# LED_Multichanel_bulb.net
KiCad netlist of a schematic drawn in EasyEDA Pro
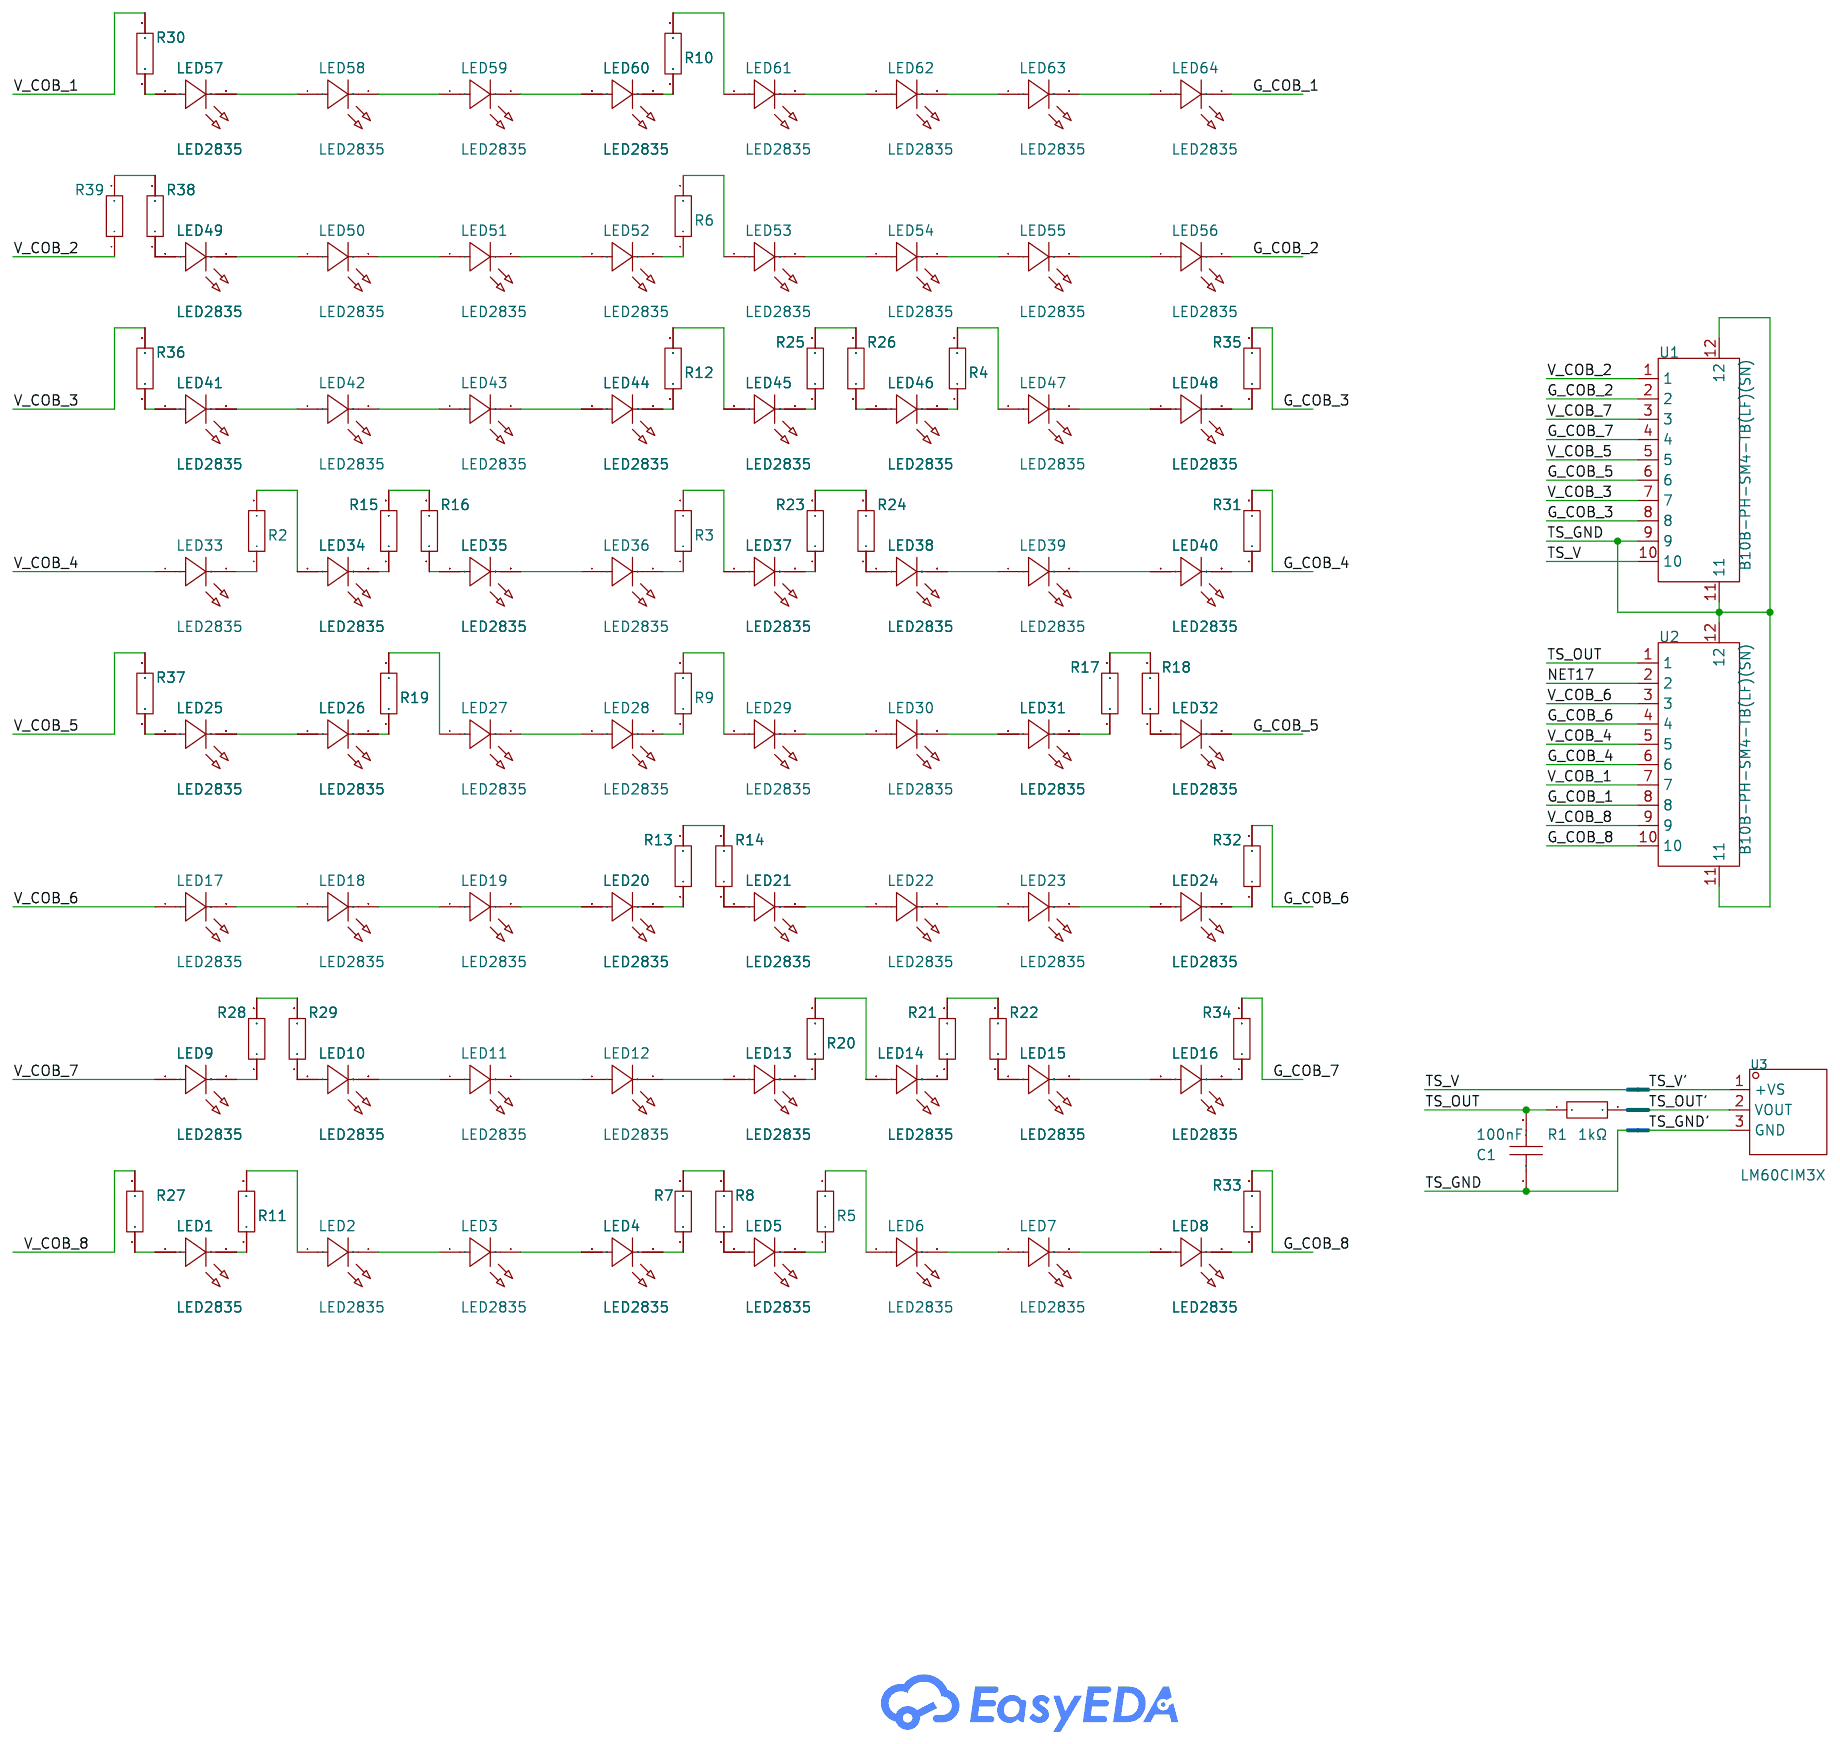
[diagram p0: schematic sheet]

(export (version "E")
  (design (tool "Eeschema 10.0.6"))
  (components
    (comp (ref "C1")
      (value "100nF")
      (footprint "easyedapro:C0805")
      (libsource (lib "easyedapro") (part "CAP"))
    )
    (comp (ref "LED1")
      (value "LED2835")
      (footprint "easyedapro:LED-SMD_L3.5-W2.8_JE2835APO-N-0001A0000-N0000001")
      (fields (field (name "Manufacturer") "WOLFSPEED"))
      (libsource (lib "easyedapro") (part "JE2835APO-N-0001A0000-N0000001"))
    )
    (comp (ref "LED2")
      (value "LED2835")
      (footprint "easyedapro:LED-SMD_L3.5-W2.8_JE2835APO-N-0001A0000-N0000001")
      (fields (field (name "Manufacturer") "WOLFSPEED"))
      (libsource (lib "easyedapro") (part "JE2835APO-N-0001A0000-N0000001"))
    )
    (comp (ref "LED3")
      (value "LED2835")
      (footprint "easyedapro:LED-SMD_L3.5-W2.8_JE2835APO-N-0001A0000-N0000001")
      (fields (field (name "Manufacturer") "WOLFSPEED"))
      (libsource (lib "easyedapro") (part "JE2835APO-N-0001A0000-N0000001"))
    )
    (comp (ref "LED4")
      (value "LED2835")
      (footprint "easyedapro:LED-SMD_L3.5-W2.8_JE2835APO-N-0001A0000-N0000001")
      (fields (field (name "Manufacturer") "WOLFSPEED"))
      (libsource (lib "easyedapro") (part "JE2835APO-N-0001A0000-N0000001"))
    )
    (comp (ref "LED5")
      (value "LED2835")
      (footprint "easyedapro:LED-SMD_L3.5-W2.8_JE2835APO-N-0001A0000-N0000001")
      (fields (field (name "Manufacturer") "WOLFSPEED"))
      (libsource (lib "easyedapro") (part "JE2835APO-N-0001A0000-N0000001"))
    )
    (comp (ref "LED6")
      (value "LED2835")
      (footprint "easyedapro:LED-SMD_L3.5-W2.8_JE2835APO-N-0001A0000-N0000001")
      (fields (field (name "Manufacturer") "WOLFSPEED"))
      (libsource (lib "easyedapro") (part "JE2835APO-N-0001A0000-N0000001"))
    )
    (comp (ref "LED7")
      (value "LED2835")
      (footprint "easyedapro:LED-SMD_L3.5-W2.8_JE2835APO-N-0001A0000-N0000001")
      (fields (field (name "Manufacturer") "WOLFSPEED"))
      (libsource (lib "easyedapro") (part "JE2835APO-N-0001A0000-N0000001"))
    )
    (comp (ref "LED8")
      (value "LED2835")
      (footprint "easyedapro:LED-SMD_L3.5-W2.8_JE2835APO-N-0001A0000-N0000001")
      (fields (field (name "Manufacturer") "WOLFSPEED"))
      (libsource (lib "easyedapro") (part "JE2835APO-N-0001A0000-N0000001"))
    )
    (comp (ref "LED9")
      (value "LED2835")
      (footprint "easyedapro:LED-SMD_L3.5-W2.8_JE2835APO-N-0001A0000-N0000001")
      (fields (field (name "Manufacturer") "WOLFSPEED"))
      (libsource (lib "easyedapro") (part "JE2835APO-N-0001A0000-N0000001"))
    )
    (comp (ref "LED10")
      (value "LED2835")
      (footprint "easyedapro:LED-SMD_L3.5-W2.8_JE2835APO-N-0001A0000-N0000001")
      (fields (field (name "Manufacturer") "WOLFSPEED"))
      (libsource (lib "easyedapro") (part "JE2835APO-N-0001A0000-N0000001"))
    )
    (comp (ref "LED11")
      (value "LED2835")
      (footprint "easyedapro:LED-SMD_L3.5-W2.8_JE2835APO-N-0001A0000-N0000001")
      (fields (field (name "Manufacturer") "WOLFSPEED"))
      (libsource (lib "easyedapro") (part "JE2835APO-N-0001A0000-N0000001"))
    )
    (comp (ref "LED12")
      (value "LED2835")
      (footprint "easyedapro:LED-SMD_L3.5-W2.8_JE2835APO-N-0001A0000-N0000001")
      (fields (field (name "Manufacturer") "WOLFSPEED"))
      (libsource (lib "easyedapro") (part "JE2835APO-N-0001A0000-N0000001"))
    )
    (comp (ref "LED13")
      (value "LED2835")
      (footprint "easyedapro:LED-SMD_L3.5-W2.8_JE2835APO-N-0001A0000-N0000001")
      (fields (field (name "Manufacturer") "WOLFSPEED"))
      (libsource (lib "easyedapro") (part "JE2835APO-N-0001A0000-N0000001"))
    )
    (comp (ref "LED14")
      (value "LED2835")
      (footprint "easyedapro:LED-SMD_L3.5-W2.8_JE2835APO-N-0001A0000-N0000001")
      (fields (field (name "Manufacturer") "WOLFSPEED"))
      (libsource (lib "easyedapro") (part "JE2835APO-N-0001A0000-N0000001"))
    )
    (comp (ref "LED15")
      (value "LED2835")
      (footprint "easyedapro:LED-SMD_L3.5-W2.8_JE2835APO-N-0001A0000-N0000001")
      (fields (field (name "Manufacturer") "WOLFSPEED"))
      (libsource (lib "easyedapro") (part "JE2835APO-N-0001A0000-N0000001"))
    )
    (comp (ref "LED16")
      (value "LED2835")
      (footprint "easyedapro:LED-SMD_L3.5-W2.8_JE2835APO-N-0001A0000-N0000001")
      (fields (field (name "Manufacturer") "WOLFSPEED"))
      (libsource (lib "easyedapro") (part "JE2835APO-N-0001A0000-N0000001"))
    )
    (comp (ref "LED17")
      (value "LED2835")
      (footprint "easyedapro:LED-SMD_L3.5-W2.8_JE2835APO-N-0001A0000-N0000001")
      (fields (field (name "Manufacturer") "WOLFSPEED"))
      (libsource (lib "easyedapro") (part "JE2835APO-N-0001A0000-N0000001"))
    )
    (comp (ref "LED18")
      (value "LED2835")
      (footprint "easyedapro:LED-SMD_L3.5-W2.8_JE2835APO-N-0001A0000-N0000001")
      (fields (field (name "Manufacturer") "WOLFSPEED"))
      (libsource (lib "easyedapro") (part "JE2835APO-N-0001A0000-N0000001"))
    )
    (comp (ref "LED19")
      (value "LED2835")
      (footprint "easyedapro:LED-SMD_L3.5-W2.8_JE2835APO-N-0001A0000-N0000001")
      (fields (field (name "Manufacturer") "WOLFSPEED"))
      (libsource (lib "easyedapro") (part "JE2835APO-N-0001A0000-N0000001"))
    )
    (comp (ref "LED20")
      (value "LED2835")
      (footprint "easyedapro:LED-SMD_L3.5-W2.8_JE2835APO-N-0001A0000-N0000001")
      (fields (field (name "Manufacturer") "WOLFSPEED"))
      (libsource (lib "easyedapro") (part "JE2835APO-N-0001A0000-N0000001"))
    )
    (comp (ref "LED21")
      (value "LED2835")
      (footprint "easyedapro:LED-SMD_L3.5-W2.8_JE2835APO-N-0001A0000-N0000001")
      (fields (field (name "Manufacturer") "WOLFSPEED"))
      (libsource (lib "easyedapro") (part "JE2835APO-N-0001A0000-N0000001"))
    )
    (comp (ref "LED22")
      (value "LED2835")
      (footprint "easyedapro:LED-SMD_L3.5-W2.8_JE2835APO-N-0001A0000-N0000001")
      (fields (field (name "Manufacturer") "WOLFSPEED"))
      (libsource (lib "easyedapro") (part "JE2835APO-N-0001A0000-N0000001"))
    )
    (comp (ref "LED23")
      (value "LED2835")
      (footprint "easyedapro:LED-SMD_L3.5-W2.8_JE2835APO-N-0001A0000-N0000001")
      (fields (field (name "Manufacturer") "WOLFSPEED"))
      (libsource (lib "easyedapro") (part "JE2835APO-N-0001A0000-N0000001"))
    )
    (comp (ref "LED24")
      (value "LED2835")
      (footprint "easyedapro:LED-SMD_L3.5-W2.8_JE2835APO-N-0001A0000-N0000001")
      (fields (field (name "Manufacturer") "WOLFSPEED"))
      (libsource (lib "easyedapro") (part "JE2835APO-N-0001A0000-N0000001"))
    )
    (comp (ref "LED25")
      (value "LED2835")
      (footprint "easyedapro:LED-SMD_L3.5-W2.8_JE2835APO-N-0001A0000-N0000001")
      (fields (field (name "Manufacturer") "WOLFSPEED"))
      (libsource (lib "easyedapro") (part "JE2835APO-N-0001A0000-N0000001"))
    )
    (comp (ref "LED26")
      (value "LED2835")
      (footprint "easyedapro:LED-SMD_L3.5-W2.8_JE2835APO-N-0001A0000-N0000001")
      (fields (field (name "Manufacturer") "WOLFSPEED"))
      (libsource (lib "easyedapro") (part "JE2835APO-N-0001A0000-N0000001"))
    )
    (comp (ref "LED27")
      (value "LED2835")
      (footprint "easyedapro:LED-SMD_L3.5-W2.8_JE2835APO-N-0001A0000-N0000001")
      (fields (field (name "Manufacturer") "WOLFSPEED"))
      (libsource (lib "easyedapro") (part "JE2835APO-N-0001A0000-N0000001"))
    )
    (comp (ref "LED28")
      (value "LED2835")
      (footprint "easyedapro:LED-SMD_L3.5-W2.8_JE2835APO-N-0001A0000-N0000001")
      (fields (field (name "Manufacturer") "WOLFSPEED"))
      (libsource (lib "easyedapro") (part "JE2835APO-N-0001A0000-N0000001"))
    )
    (comp (ref "LED29")
      (value "LED2835")
      (footprint "easyedapro:LED-SMD_L3.5-W2.8_JE2835APO-N-0001A0000-N0000001")
      (fields (field (name "Manufacturer") "WOLFSPEED"))
      (libsource (lib "easyedapro") (part "JE2835APO-N-0001A0000-N0000001"))
    )
    (comp (ref "LED30")
      (value "LED2835")
      (footprint "easyedapro:LED-SMD_L3.5-W2.8_JE2835APO-N-0001A0000-N0000001")
      (fields (field (name "Manufacturer") "WOLFSPEED"))
      (libsource (lib "easyedapro") (part "JE2835APO-N-0001A0000-N0000001"))
    )
    (comp (ref "LED31")
      (value "LED2835")
      (footprint "easyedapro:LED-SMD_L3.5-W2.8_JE2835APO-N-0001A0000-N0000001")
      (fields (field (name "Manufacturer") "WOLFSPEED"))
      (libsource (lib "easyedapro") (part "JE2835APO-N-0001A0000-N0000001"))
    )
    (comp (ref "LED32")
      (value "LED2835")
      (footprint "easyedapro:LED-SMD_L3.5-W2.8_JE2835APO-N-0001A0000-N0000001")
      (fields (field (name "Manufacturer") "WOLFSPEED"))
      (libsource (lib "easyedapro") (part "JE2835APO-N-0001A0000-N0000001"))
    )
    (comp (ref "LED33")
      (value "LED2835")
      (footprint "easyedapro:LED-SMD_L3.5-W2.8_JE2835APO-N-0001A0000-N0000001")
      (fields (field (name "Manufacturer") "WOLFSPEED"))
      (libsource (lib "easyedapro") (part "JE2835APO-N-0001A0000-N0000001"))
    )
    (comp (ref "LED34")
      (value "LED2835")
      (footprint "easyedapro:LED-SMD_L3.5-W2.8_JE2835APO-N-0001A0000-N0000001")
      (fields (field (name "Manufacturer") "WOLFSPEED"))
      (libsource (lib "easyedapro") (part "JE2835APO-N-0001A0000-N0000001"))
    )
    (comp (ref "LED35")
      (value "LED2835")
      (footprint "easyedapro:LED-SMD_L3.5-W2.8_JE2835APO-N-0001A0000-N0000001")
      (fields (field (name "Manufacturer") "WOLFSPEED"))
      (libsource (lib "easyedapro") (part "JE2835APO-N-0001A0000-N0000001"))
    )
    (comp (ref "LED36")
      (value "LED2835")
      (footprint "easyedapro:LED-SMD_L3.5-W2.8_JE2835APO-N-0001A0000-N0000001")
      (fields (field (name "Manufacturer") "WOLFSPEED"))
      (libsource (lib "easyedapro") (part "JE2835APO-N-0001A0000-N0000001"))
    )
    (comp (ref "LED37")
      (value "LED2835")
      (footprint "easyedapro:LED-SMD_L3.5-W2.8_JE2835APO-N-0001A0000-N0000001")
      (fields (field (name "Manufacturer") "WOLFSPEED"))
      (libsource (lib "easyedapro") (part "JE2835APO-N-0001A0000-N0000001"))
    )
    (comp (ref "LED38")
      (value "LED2835")
      (footprint "easyedapro:LED-SMD_L3.5-W2.8_JE2835APO-N-0001A0000-N0000001")
      (fields (field (name "Manufacturer") "WOLFSPEED"))
      (libsource (lib "easyedapro") (part "JE2835APO-N-0001A0000-N0000001"))
    )
    (comp (ref "LED39")
      (value "LED2835")
      (footprint "easyedapro:LED-SMD_L3.5-W2.8_JE2835APO-N-0001A0000-N0000001")
      (fields (field (name "Manufacturer") "WOLFSPEED"))
      (libsource (lib "easyedapro") (part "JE2835APO-N-0001A0000-N0000001"))
    )
    (comp (ref "LED40")
      (value "LED2835")
      (footprint "easyedapro:LED-SMD_L3.5-W2.8_JE2835APO-N-0001A0000-N0000001")
      (fields (field (name "Manufacturer") "WOLFSPEED"))
      (libsource (lib "easyedapro") (part "JE2835APO-N-0001A0000-N0000001"))
    )
    (comp (ref "LED41")
      (value "LED2835")
      (footprint "easyedapro:LED-SMD_L3.5-W2.8_JE2835APO-N-0001A0000-N0000001")
      (fields (field (name "Manufacturer") "WOLFSPEED"))
      (libsource (lib "easyedapro") (part "JE2835APO-N-0001A0000-N0000001"))
    )
    (comp (ref "LED42")
      (value "LED2835")
      (footprint "easyedapro:LED-SMD_L3.5-W2.8_JE2835APO-N-0001A0000-N0000001")
      (fields (field (name "Manufacturer") "WOLFSPEED"))
      (libsource (lib "easyedapro") (part "JE2835APO-N-0001A0000-N0000001"))
    )
    (comp (ref "LED43")
      (value "LED2835")
      (footprint "easyedapro:LED-SMD_L3.5-W2.8_JE2835APO-N-0001A0000-N0000001")
      (fields (field (name "Manufacturer") "WOLFSPEED"))
      (libsource (lib "easyedapro") (part "JE2835APO-N-0001A0000-N0000001"))
    )
    (comp (ref "LED44")
      (value "LED2835")
      (footprint "easyedapro:LED-SMD_L3.5-W2.8_JE2835APO-N-0001A0000-N0000001")
      (fields (field (name "Manufacturer") "WOLFSPEED"))
      (libsource (lib "easyedapro") (part "JE2835APO-N-0001A0000-N0000001"))
    )
    (comp (ref "LED45")
      (value "LED2835")
      (footprint "easyedapro:LED-SMD_L3.5-W2.8_JE2835APO-N-0001A0000-N0000001")
      (fields (field (name "Manufacturer") "WOLFSPEED"))
      (libsource (lib "easyedapro") (part "JE2835APO-N-0001A0000-N0000001"))
    )
    (comp (ref "LED46")
      (value "LED2835")
      (footprint "easyedapro:LED-SMD_L3.5-W2.8_JE2835APO-N-0001A0000-N0000001")
      (fields (field (name "Manufacturer") "WOLFSPEED"))
      (libsource (lib "easyedapro") (part "JE2835APO-N-0001A0000-N0000001"))
    )
    (comp (ref "LED47")
      (value "LED2835")
      (footprint "easyedapro:LED-SMD_L3.5-W2.8_JE2835APO-N-0001A0000-N0000001")
      (fields (field (name "Manufacturer") "WOLFSPEED"))
      (libsource (lib "easyedapro") (part "JE2835APO-N-0001A0000-N0000001"))
    )
    (comp (ref "LED48")
      (value "LED2835")
      (footprint "easyedapro:LED-SMD_L3.5-W2.8_JE2835APO-N-0001A0000-N0000001")
      (fields (field (name "Manufacturer") "WOLFSPEED"))
      (libsource (lib "easyedapro") (part "JE2835APO-N-0001A0000-N0000001"))
    )
    (comp (ref "LED49")
      (value "LED2835")
      (footprint "easyedapro:LED-SMD_L3.5-W2.8_JE2835APO-N-0001A0000-N0000001")
      (fields (field (name "Manufacturer") "WOLFSPEED"))
      (libsource (lib "easyedapro") (part "JE2835APO-N-0001A0000-N0000001"))
    )
    (comp (ref "LED50")
      (value "LED2835")
      (footprint "easyedapro:LED-SMD_L3.5-W2.8_JE2835APO-N-0001A0000-N0000001")
      (fields (field (name "Manufacturer") "WOLFSPEED"))
      (libsource (lib "easyedapro") (part "JE2835APO-N-0001A0000-N0000001"))
    )
    (comp (ref "LED51")
      (value "LED2835")
      (footprint "easyedapro:LED-SMD_L3.5-W2.8_JE2835APO-N-0001A0000-N0000001")
      (fields (field (name "Manufacturer") "WOLFSPEED"))
      (libsource (lib "easyedapro") (part "JE2835APO-N-0001A0000-N0000001"))
    )
    (comp (ref "LED52")
      (value "LED2835")
      (footprint "easyedapro:LED-SMD_L3.5-W2.8_JE2835APO-N-0001A0000-N0000001")
      (fields (field (name "Manufacturer") "WOLFSPEED"))
      (libsource (lib "easyedapro") (part "JE2835APO-N-0001A0000-N0000001"))
    )
    (comp (ref "LED53")
      (value "LED2835")
      (footprint "easyedapro:LED-SMD_L3.5-W2.8_JE2835APO-N-0001A0000-N0000001")
      (fields (field (name "Manufacturer") "WOLFSPEED"))
      (libsource (lib "easyedapro") (part "JE2835APO-N-0001A0000-N0000001"))
    )
    (comp (ref "LED54")
      (value "LED2835")
      (footprint "easyedapro:LED-SMD_L3.5-W2.8_JE2835APO-N-0001A0000-N0000001")
      (fields (field (name "Manufacturer") "WOLFSPEED"))
      (libsource (lib "easyedapro") (part "JE2835APO-N-0001A0000-N0000001"))
    )
    (comp (ref "LED55")
      (value "LED2835")
      (footprint "easyedapro:LED-SMD_L3.5-W2.8_JE2835APO-N-0001A0000-N0000001")
      (fields (field (name "Manufacturer") "WOLFSPEED"))
      (libsource (lib "easyedapro") (part "JE2835APO-N-0001A0000-N0000001"))
    )
    (comp (ref "LED56")
      (value "LED2835")
      (footprint "easyedapro:LED-SMD_L3.5-W2.8_JE2835APO-N-0001A0000-N0000001")
      (fields (field (name "Manufacturer") "WOLFSPEED"))
      (libsource (lib "easyedapro") (part "JE2835APO-N-0001A0000-N0000001"))
    )
    (comp (ref "LED57")
      (value "LED2835")
      (footprint "easyedapro:LED-SMD_L3.5-W2.8_JE2835APO-N-0001A0000-N0000001")
      (fields (field (name "Manufacturer") "WOLFSPEED"))
      (libsource (lib "easyedapro") (part "JE2835APO-N-0001A0000-N0000001"))
    )
    (comp (ref "LED58")
      (value "LED2835")
      (footprint "easyedapro:LED-SMD_L3.5-W2.8_JE2835APO-N-0001A0000-N0000001")
      (fields (field (name "Manufacturer") "WOLFSPEED"))
      (libsource (lib "easyedapro") (part "JE2835APO-N-0001A0000-N0000001"))
    )
    (comp (ref "LED59")
      (value "LED2835")
      (footprint "easyedapro:LED-SMD_L3.5-W2.8_JE2835APO-N-0001A0000-N0000001")
      (fields (field (name "Manufacturer") "WOLFSPEED"))
      (libsource (lib "easyedapro") (part "JE2835APO-N-0001A0000-N0000001"))
    )
    (comp (ref "LED60")
      (value "LED2835")
      (footprint "easyedapro:LED-SMD_L3.5-W2.8_JE2835APO-N-0001A0000-N0000001")
      (fields (field (name "Manufacturer") "WOLFSPEED"))
      (libsource (lib "easyedapro") (part "JE2835APO-N-0001A0000-N0000001"))
    )
    (comp (ref "LED61")
      (value "LED2835")
      (footprint "easyedapro:LED-SMD_L3.5-W2.8_JE2835APO-N-0001A0000-N0000001")
      (fields (field (name "Manufacturer") "WOLFSPEED"))
      (libsource (lib "easyedapro") (part "JE2835APO-N-0001A0000-N0000001"))
    )
    (comp (ref "LED62")
      (value "LED2835")
      (footprint "easyedapro:LED-SMD_L3.5-W2.8_JE2835APO-N-0001A0000-N0000001")
      (fields (field (name "Manufacturer") "WOLFSPEED"))
      (libsource (lib "easyedapro") (part "JE2835APO-N-0001A0000-N0000001"))
    )
    (comp (ref "LED63")
      (value "LED2835")
      (footprint "easyedapro:LED-SMD_L3.5-W2.8_JE2835APO-N-0001A0000-N0000001")
      (fields (field (name "Manufacturer") "WOLFSPEED"))
      (libsource (lib "easyedapro") (part "JE2835APO-N-0001A0000-N0000001"))
    )
    (comp (ref "LED64")
      (value "LED2835")
      (footprint "easyedapro:LED-SMD_L3.5-W2.8_JE2835APO-N-0001A0000-N0000001")
      (fields (field (name "Manufacturer") "WOLFSPEED"))
      (libsource (lib "easyedapro") (part "JE2835APO-N-0001A0000-N0000001"))
    )
    (comp (ref "R1")
      (value "1kΩ")
      (footprint "easyedapro:R0805")
      (fields (field (name "Manufacturer Part") "ERA6AEB102V") (field (name "Manufacturer") "PANASONIC(松下)"))
      (libsource (lib "easyedapro") (part "ERA-6AEB102V"))
    )
    (comp (ref "R2")
      (value "10kΩ")
      (footprint "easyedapro:R0603")
      (libsource (lib "easyedapro") (part "Res"))
    )
    (comp (ref "R3")
      (value "10kΩ")
      (footprint "easyedapro:R0603")
      (libsource (lib "easyedapro") (part "Res"))
    )
    (comp (ref "R4")
      (value "10kΩ")
      (footprint "easyedapro:R0603")
      (libsource (lib "easyedapro") (part "Res"))
    )
    (comp (ref "R5")
      (value "10kΩ")
      (footprint "easyedapro:R0603")
      (libsource (lib "easyedapro") (part "Res"))
    )
    (comp (ref "R6")
      (value "10kΩ")
      (footprint "easyedapro:R0603")
      (libsource (lib "easyedapro") (part "Res"))
    )
    (comp (ref "R7")
      (value "10kΩ")
      (footprint "easyedapro:R0603")
      (libsource (lib "easyedapro") (part "Res"))
    )
    (comp (ref "R8")
      (value "10kΩ")
      (footprint "easyedapro:R0603")
      (libsource (lib "easyedapro") (part "Res"))
    )
    (comp (ref "R9")
      (value "10kΩ")
      (footprint "easyedapro:R0603")
      (libsource (lib "easyedapro") (part "Res"))
    )
    (comp (ref "R10")
      (value "10kΩ")
      (footprint "easyedapro:R0603")
      (libsource (lib "easyedapro") (part "Res"))
    )
    (comp (ref "R11")
      (value "10kΩ")
      (footprint "easyedapro:R0603")
      (libsource (lib "easyedapro") (part "Res"))
    )
    (comp (ref "R12")
      (value "10kΩ")
      (footprint "easyedapro:R0603")
      (libsource (lib "easyedapro") (part "Res"))
    )
    (comp (ref "R13")
      (value "10kΩ")
      (footprint "easyedapro:R0603")
      (libsource (lib "easyedapro") (part "Res"))
    )
    (comp (ref "R14")
      (value "10kΩ")
      (footprint "easyedapro:R0603")
      (libsource (lib "easyedapro") (part "Res"))
    )
    (comp (ref "R15")
      (value "10kΩ")
      (footprint "easyedapro:R0603")
      (libsource (lib "easyedapro") (part "Res"))
    )
    (comp (ref "R16")
      (value "10kΩ")
      (footprint "easyedapro:R0603")
      (libsource (lib "easyedapro") (part "Res"))
    )
    (comp (ref "R17")
      (value "10kΩ")
      (footprint "easyedapro:R0603")
      (libsource (lib "easyedapro") (part "Res"))
    )
    (comp (ref "R18")
      (value "10kΩ")
      (footprint "easyedapro:R0603")
      (libsource (lib "easyedapro") (part "Res"))
    )
    (comp (ref "R19")
      (value "10kΩ")
      (footprint "easyedapro:R0603")
      (libsource (lib "easyedapro") (part "Res"))
    )
    (comp (ref "R20")
      (value "10kΩ")
      (footprint "easyedapro:R0603")
      (libsource (lib "easyedapro") (part "Res"))
    )
    (comp (ref "R21")
      (value "10kΩ")
      (footprint "easyedapro:R0603")
      (libsource (lib "easyedapro") (part "Res"))
    )
    (comp (ref "R22")
      (value "10kΩ")
      (footprint "easyedapro:R0603")
      (libsource (lib "easyedapro") (part "Res"))
    )
    (comp (ref "R23")
      (value "10kΩ")
      (footprint "easyedapro:R0603")
      (libsource (lib "easyedapro") (part "Res"))
    )
    (comp (ref "R24")
      (value "10kΩ")
      (footprint "easyedapro:R0603")
      (libsource (lib "easyedapro") (part "Res"))
    )
    (comp (ref "R25")
      (value "10kΩ")
      (footprint "easyedapro:R0603")
      (libsource (lib "easyedapro") (part "Res"))
    )
    (comp (ref "R26")
      (value "10kΩ")
      (footprint "easyedapro:R0603")
      (libsource (lib "easyedapro") (part "Res"))
    )
    (comp (ref "R27")
      (value "10kΩ")
      (footprint "easyedapro:R0603")
      (libsource (lib "easyedapro") (part "Res"))
    )
    (comp (ref "R28")
      (value "10kΩ")
      (footprint "easyedapro:R0603")
      (libsource (lib "easyedapro") (part "Res"))
    )
    (comp (ref "R29")
      (value "10kΩ")
      (footprint "easyedapro:R0603")
      (libsource (lib "easyedapro") (part "Res"))
    )
    (comp (ref "R30")
      (value "10kΩ")
      (footprint "easyedapro:R0603")
      (libsource (lib "easyedapro") (part "Res"))
    )
    (comp (ref "R31")
      (value "10kΩ")
      (footprint "easyedapro:R0603")
      (libsource (lib "easyedapro") (part "Res"))
    )
    (comp (ref "R32")
      (value "10kΩ")
      (footprint "easyedapro:R0603")
      (libsource (lib "easyedapro") (part "Res"))
    )
    (comp (ref "R33")
      (value "10kΩ")
      (footprint "easyedapro:R0603")
      (libsource (lib "easyedapro") (part "Res"))
    )
    (comp (ref "R34")
      (value "10kΩ")
      (footprint "easyedapro:R0603")
      (libsource (lib "easyedapro") (part "Res"))
    )
    (comp (ref "R35")
      (value "10kΩ")
      (footprint "easyedapro:R0603")
      (libsource (lib "easyedapro") (part "Res"))
    )
    (comp (ref "R36")
      (value "10kΩ")
      (footprint "easyedapro:R0603")
      (libsource (lib "easyedapro") (part "Res"))
    )
    (comp (ref "R37")
      (value "10kΩ")
      (footprint "easyedapro:R0603")
      (libsource (lib "easyedapro") (part "Res"))
    )
    (comp (ref "R38")
      (value "10kΩ")
      (footprint "easyedapro:R0603")
      (libsource (lib "easyedapro") (part "Res"))
    )
    (comp (ref "R39")
      (value "10kΩ")
      (footprint "easyedapro:R0603")
      (libsource (lib "easyedapro") (part "Res"))
    )
    (comp (ref "U1")
      (value "B10B-PH-SM4-TB(LF)(SN)")
      (footprint "easyedapro:CONN-SMD_B10B-PH-SM4-TB-LF-SN")
      (fields (field (name "Manufacturer") "JST"))
      (libsource (lib "easyedapro") (part "B10B-PH-SM4-TB(LF)(SN)"))
    )
    (comp (ref "U2")
      (value "B10B-PH-SM4-TB(LF)(SN)")
      (footprint "easyedapro:CONN-SMD_B10B-PH-SM4-TB-LF-SN")
      (fields (field (name "Manufacturer") "JST"))
      (libsource (lib "easyedapro") (part "B10B-PH-SM4-TB(LF)(SN)"))
    )
    (comp (ref "U3")
      (value "LM60CIM3X")
      (footprint "easyedapro:SOT-23-3_L2.9-W1.3-P1.90-LS2.4-BR")
      (description "Supply Voltage:2.7V~10V Supply Voltage:2.7V~10V")
      (fields (field (name "Manufacturer") "TI(德州仪器)"))
      (libsource (lib "easyedapro") (part "LM60CIM3X/NOPB"))
    )
  )
  (nets
    (net (code "1") (name "/G_COB_1") (class "Default")
      (node (ref "LED64") (pin "2") (pinfunction "C_2") (pintype "unspecified"))
      (node (ref "U2") (pin "8") (pinfunction "8_8") (pintype "unspecified"))
    )
    (net (code "2") (name "/G_COB_2") (class "Default")
      (node (ref "LED56") (pin "2") (pinfunction "C_2") (pintype "unspecified"))
      (node (ref "U1") (pin "2") (pinfunction "2_2") (pintype "unspecified"))
    )
    (net (code "3") (name "/G_COB_3") (class "Default")
      (node (ref "R35") (pin "2") (pinfunction "2_2") (pintype "input"))
      (node (ref "U1") (pin "8") (pinfunction "8_8") (pintype "unspecified"))
    )
    (net (code "4") (name "/G_COB_4") (class "Default")
      (node (ref "R31") (pin "2") (pinfunction "2_2") (pintype "input"))
      (node (ref "U2") (pin "6") (pinfunction "6_6") (pintype "unspecified"))
    )
    (net (code "5") (name "/G_COB_5") (class "Default")
      (node (ref "LED32") (pin "2") (pinfunction "C_2") (pintype "unspecified"))
      (node (ref "U1") (pin "6") (pinfunction "6_6") (pintype "unspecified"))
    )
    (net (code "6") (name "/G_COB_6") (class "Default")
      (node (ref "R32") (pin "2") (pinfunction "2_2") (pintype "input"))
      (node (ref "U2") (pin "4") (pinfunction "4_4") (pintype "unspecified"))
    )
    (net (code "7") (name "/G_COB_7") (class "Default")
      (node (ref "R34") (pin "2") (pinfunction "2_2") (pintype "input"))
      (node (ref "U1") (pin "4") (pinfunction "4_4") (pintype "unspecified"))
    )
    (net (code "8") (name "/G_COB_8") (class "Default")
      (node (ref "R33") (pin "2") (pinfunction "2_2") (pintype "input"))
      (node (ref "U2") (pin "10") (pinfunction "10_10") (pintype "unspecified"))
    )
    (net (code "9") (name "/NET17") (class "Default")
      (node (ref "U2") (pin "2") (pinfunction "2_2") (pintype "unspecified"))
    )
    (net (code "10") (name "/TS_GND") (class "Default")
      (node (ref "C1") (pin "1") (pinfunction "1_1") (pintype "input"))
      (node (ref "U1") (pin "11") (pinfunction "11_11") (pintype "unspecified"))
      (node (ref "U1") (pin "12") (pinfunction "12_12") (pintype "unspecified"))
      (node (ref "U1") (pin "9") (pinfunction "9_9") (pintype "unspecified"))
      (node (ref "U2") (pin "11") (pinfunction "11_11") (pintype "unspecified"))
      (node (ref "U2") (pin "12") (pinfunction "12_12") (pintype "unspecified"))
    )
    (net (code "11") (name "/TS_GND'") (class "Default")
      (node (ref "U3") (pin "3") (pinfunction "GND_3") (pintype "input"))
    )
    (net (code "12") (name "/TS_OUT") (class "Default")
      (node (ref "C1") (pin "2") (pinfunction "2_2") (pintype "input"))
      (node (ref "R1") (pin "1") (pinfunction "1_1") (pintype "unspecified"))
      (node (ref "U2") (pin "1") (pinfunction "1_1") (pintype "unspecified"))
    )
    (net (code "13") (name "/TS_OUT'") (class "Default")
      (node (ref "U3") (pin "2") (pinfunction "VOUT_2") (pintype "input"))
    )
    (net (code "14") (name "/TS_V") (class "Default")
      (node (ref "U1") (pin "10") (pinfunction "10_10") (pintype "unspecified"))
    )
    (net (code "15") (name "/TS_V'") (class "Default")
      (node (ref "U3") (pin "1") (pinfunction "+VS_1") (pintype "input"))
    )
    (net (code "16") (name "/V_COB_1") (class "Default")
      (node (ref "R30") (pin "2") (pinfunction "2_2") (pintype "input"))
      (node (ref "U2") (pin "7") (pinfunction "7_7") (pintype "unspecified"))
    )
    (net (code "17") (name "/V_COB_2") (class "Default")
      (node (ref "R39") (pin "1") (pinfunction "1_1") (pintype "input"))
      (node (ref "U1") (pin "1") (pinfunction "1_1") (pintype "unspecified"))
    )
    (net (code "18") (name "/V_COB_3") (class "Default")
      (node (ref "R36") (pin "2") (pinfunction "2_2") (pintype "input"))
      (node (ref "U1") (pin "7") (pinfunction "7_7") (pintype "unspecified"))
    )
    (net (code "19") (name "/V_COB_4") (class "Default")
      (node (ref "LED33") (pin "1") (pinfunction "A_1") (pintype "unspecified"))
      (node (ref "U2") (pin "5") (pinfunction "5_5") (pintype "unspecified"))
    )
    (net (code "20") (name "/V_COB_5") (class "Default")
      (node (ref "R37") (pin "2") (pinfunction "2_2") (pintype "input"))
      (node (ref "U1") (pin "5") (pinfunction "5_5") (pintype "unspecified"))
    )
    (net (code "21") (name "/V_COB_6") (class "Default")
      (node (ref "LED17") (pin "1") (pinfunction "A_1") (pintype "unspecified"))
      (node (ref "U2") (pin "3") (pinfunction "3_3") (pintype "unspecified"))
    )
    (net (code "22") (name "/V_COB_7") (class "Default")
      (node (ref "LED9") (pin "1") (pinfunction "A_1") (pintype "unspecified"))
      (node (ref "U1") (pin "3") (pinfunction "3_3") (pintype "unspecified"))
    )
    (net (code "23") (name "/V_COB_8") (class "Default")
      (node (ref "R27") (pin "2") (pinfunction "2_2") (pintype "input"))
      (node (ref "U2") (pin "9") (pinfunction "9_9") (pintype "unspecified"))
    )
    (net (code "24") (name "Net-(LED1-A)") (class "Default")
      (node (ref "LED1") (pin "1") (pinfunction "A_1") (pintype "unspecified"))
      (node (ref "R27") (pin "1") (pinfunction "1_1") (pintype "input"))
    )
    (net (code "25") (name "Net-(LED1-C)") (class "Default")
      (node (ref "LED1") (pin "2") (pinfunction "C_2") (pintype "unspecified"))
      (node (ref "R11") (pin "1") (pinfunction "1_1") (pintype "input"))
    )
    (net (code "26") (name "Net-(LED2-A)") (class "Default")
      (node (ref "LED2") (pin "1") (pinfunction "A_1") (pintype "unspecified"))
      (node (ref "R11") (pin "2") (pinfunction "2_2") (pintype "input"))
    )
    (net (code "27") (name "Net-(LED2-C)") (class "Default")
      (node (ref "LED2") (pin "2") (pinfunction "C_2") (pintype "unspecified"))
      (node (ref "LED3") (pin "1") (pinfunction "A_1") (pintype "unspecified"))
    )
    (net (code "28") (name "Net-(LED3-C)") (class "Default")
      (node (ref "LED3") (pin "2") (pinfunction "C_2") (pintype "unspecified"))
      (node (ref "LED4") (pin "1") (pinfunction "A_1") (pintype "unspecified"))
    )
    (net (code "29") (name "Net-(LED4-C)") (class "Default")
      (node (ref "LED4") (pin "2") (pinfunction "C_2") (pintype "unspecified"))
      (node (ref "R7") (pin "1") (pinfunction "1_1") (pintype "input"))
    )
    (net (code "30") (name "Net-(LED5-A)") (class "Default")
      (node (ref "LED5") (pin "1") (pinfunction "A_1") (pintype "unspecified"))
      (node (ref "R8") (pin "1") (pinfunction "1_1") (pintype "input"))
    )
    (net (code "31") (name "Net-(LED5-C)") (class "Default")
      (node (ref "LED5") (pin "2") (pinfunction "C_2") (pintype "unspecified"))
      (node (ref "R5") (pin "1") (pinfunction "1_1") (pintype "input"))
    )
    (net (code "32") (name "Net-(LED6-A)") (class "Default")
      (node (ref "LED6") (pin "1") (pinfunction "A_1") (pintype "unspecified"))
      (node (ref "R5") (pin "2") (pinfunction "2_2") (pintype "input"))
    )
    (net (code "33") (name "Net-(LED6-C)") (class "Default")
      (node (ref "LED6") (pin "2") (pinfunction "C_2") (pintype "unspecified"))
      (node (ref "LED7") (pin "1") (pinfunction "A_1") (pintype "unspecified"))
    )
    (net (code "34") (name "Net-(LED7-C)") (class "Default")
      (node (ref "LED7") (pin "2") (pinfunction "C_2") (pintype "unspecified"))
      (node (ref "LED8") (pin "1") (pinfunction "A_1") (pintype "unspecified"))
    )
    (net (code "35") (name "Net-(LED8-C)") (class "Default")
      (node (ref "LED8") (pin "2") (pinfunction "C_2") (pintype "unspecified"))
      (node (ref "R33") (pin "1") (pinfunction "1_1") (pintype "input"))
    )
    (net (code "36") (name "Net-(LED9-C)") (class "Default")
      (node (ref "LED9") (pin "2") (pinfunction "C_2") (pintype "unspecified"))
      (node (ref "R28") (pin "1") (pinfunction "1_1") (pintype "input"))
    )
    (net (code "37") (name "Net-(LED10-A)") (class "Default")
      (node (ref "LED10") (pin "1") (pinfunction "A_1") (pintype "unspecified"))
      (node (ref "R29") (pin "1") (pinfunction "1_1") (pintype "input"))
    )
    (net (code "38") (name "Net-(LED10-C)") (class "Default")
      (node (ref "LED10") (pin "2") (pinfunction "C_2") (pintype "unspecified"))
      (node (ref "LED11") (pin "1") (pinfunction "A_1") (pintype "unspecified"))
    )
    (net (code "39") (name "Net-(LED11-C)") (class "Default")
      (node (ref "LED11") (pin "2") (pinfunction "C_2") (pintype "unspecified"))
      (node (ref "LED12") (pin "1") (pinfunction "A_1") (pintype "unspecified"))
    )
    (net (code "40") (name "Net-(LED12-C)") (class "Default")
      (node (ref "LED12") (pin "2") (pinfunction "C_2") (pintype "unspecified"))
      (node (ref "LED13") (pin "1") (pinfunction "A_1") (pintype "unspecified"))
    )
    (net (code "41") (name "Net-(LED13-C)") (class "Default")
      (node (ref "LED13") (pin "2") (pinfunction "C_2") (pintype "unspecified"))
      (node (ref "R20") (pin "1") (pinfunction "1_1") (pintype "input"))
    )
    (net (code "42") (name "Net-(LED14-A)") (class "Default")
      (node (ref "LED14") (pin "1") (pinfunction "A_1") (pintype "unspecified"))
      (node (ref "R20") (pin "2") (pinfunction "2_2") (pintype "input"))
    )
    (net (code "43") (name "Net-(LED14-C)") (class "Default")
      (node (ref "LED14") (pin "2") (pinfunction "C_2") (pintype "unspecified"))
      (node (ref "R21") (pin "1") (pinfunction "1_1") (pintype "input"))
    )
    (net (code "44") (name "Net-(LED15-A)") (class "Default")
      (node (ref "LED15") (pin "1") (pinfunction "A_1") (pintype "unspecified"))
      (node (ref "R22") (pin "1") (pinfunction "1_1") (pintype "input"))
    )
    (net (code "45") (name "Net-(LED15-C)") (class "Default")
      (node (ref "LED15") (pin "2") (pinfunction "C_2") (pintype "unspecified"))
      (node (ref "LED16") (pin "1") (pinfunction "A_1") (pintype "unspecified"))
    )
    (net (code "46") (name "Net-(LED16-C)") (class "Default")
      (node (ref "LED16") (pin "2") (pinfunction "C_2") (pintype "unspecified"))
      (node (ref "R34") (pin "1") (pinfunction "1_1") (pintype "input"))
    )
    (net (code "47") (name "Net-(LED17-C)") (class "Default")
      (node (ref "LED17") (pin "2") (pinfunction "C_2") (pintype "unspecified"))
      (node (ref "LED18") (pin "1") (pinfunction "A_1") (pintype "unspecified"))
    )
    (net (code "48") (name "Net-(LED18-C)") (class "Default")
      (node (ref "LED18") (pin "2") (pinfunction "C_2") (pintype "unspecified"))
      (node (ref "LED19") (pin "1") (pinfunction "A_1") (pintype "unspecified"))
    )
    (net (code "49") (name "Net-(LED19-C)") (class "Default")
      (node (ref "LED19") (pin "2") (pinfunction "C_2") (pintype "unspecified"))
      (node (ref "LED20") (pin "1") (pinfunction "A_1") (pintype "unspecified"))
    )
    (net (code "50") (name "Net-(LED20-C)") (class "Default")
      (node (ref "LED20") (pin "2") (pinfunction "C_2") (pintype "unspecified"))
      (node (ref "R13") (pin "1") (pinfunction "1_1") (pintype "input"))
    )
    (net (code "51") (name "Net-(LED21-A)") (class "Default")
      (node (ref "LED21") (pin "1") (pinfunction "A_1") (pintype "unspecified"))
      (node (ref "R14") (pin "1") (pinfunction "1_1") (pintype "input"))
    )
    (net (code "52") (name "Net-(LED21-C)") (class "Default")
      (node (ref "LED21") (pin "2") (pinfunction "C_2") (pintype "unspecified"))
      (node (ref "LED22") (pin "1") (pinfunction "A_1") (pintype "unspecified"))
    )
    (net (code "53") (name "Net-(LED22-C)") (class "Default")
      (node (ref "LED22") (pin "2") (pinfunction "C_2") (pintype "unspecified"))
      (node (ref "LED23") (pin "1") (pinfunction "A_1") (pintype "unspecified"))
    )
    (net (code "54") (name "Net-(LED23-C)") (class "Default")
      (node (ref "LED23") (pin "2") (pinfunction "C_2") (pintype "unspecified"))
      (node (ref "LED24") (pin "1") (pinfunction "A_1") (pintype "unspecified"))
    )
    (net (code "55") (name "Net-(LED24-C)") (class "Default")
      (node (ref "LED24") (pin "2") (pinfunction "C_2") (pintype "unspecified"))
      (node (ref "R32") (pin "1") (pinfunction "1_1") (pintype "input"))
    )
    (net (code "56") (name "Net-(LED25-A)") (class "Default")
      (node (ref "LED25") (pin "1") (pinfunction "A_1") (pintype "unspecified"))
      (node (ref "R37") (pin "1") (pinfunction "1_1") (pintype "input"))
    )
    (net (code "57") (name "Net-(LED25-C)") (class "Default")
      (node (ref "LED25") (pin "2") (pinfunction "C_2") (pintype "unspecified"))
      (node (ref "LED26") (pin "1") (pinfunction "A_1") (pintype "unspecified"))
    )
    (net (code "58") (name "Net-(LED26-C)") (class "Default")
      (node (ref "LED26") (pin "2") (pinfunction "C_2") (pintype "unspecified"))
      (node (ref "R19") (pin "1") (pinfunction "1_1") (pintype "input"))
    )
    (net (code "59") (name "Net-(LED27-A)") (class "Default")
      (node (ref "LED27") (pin "1") (pinfunction "A_1") (pintype "unspecified"))
      (node (ref "R19") (pin "2") (pinfunction "2_2") (pintype "input"))
    )
    (net (code "60") (name "Net-(LED27-C)") (class "Default")
      (node (ref "LED27") (pin "2") (pinfunction "C_2") (pintype "unspecified"))
      (node (ref "LED28") (pin "1") (pinfunction "A_1") (pintype "unspecified"))
    )
    (net (code "61") (name "Net-(LED28-C)") (class "Default")
      (node (ref "LED28") (pin "2") (pinfunction "C_2") (pintype "unspecified"))
      (node (ref "R9") (pin "1") (pinfunction "1_1") (pintype "input"))
    )
    (net (code "62") (name "Net-(LED29-A)") (class "Default")
      (node (ref "LED29") (pin "1") (pinfunction "A_1") (pintype "unspecified"))
      (node (ref "R9") (pin "2") (pinfunction "2_2") (pintype "input"))
    )
    (net (code "63") (name "Net-(LED29-C)") (class "Default")
      (node (ref "LED29") (pin "2") (pinfunction "C_2") (pintype "unspecified"))
      (node (ref "LED30") (pin "1") (pinfunction "A_1") (pintype "unspecified"))
    )
    (net (code "64") (name "Net-(LED30-C)") (class "Default")
      (node (ref "LED30") (pin "2") (pinfunction "C_2") (pintype "unspecified"))
      (node (ref "LED31") (pin "1") (pinfunction "A_1") (pintype "unspecified"))
    )
    (net (code "65") (name "Net-(LED31-C)") (class "Default")
      (node (ref "LED31") (pin "2") (pinfunction "C_2") (pintype "unspecified"))
      (node (ref "R17") (pin "1") (pinfunction "1_1") (pintype "input"))
    )
    (net (code "66") (name "Net-(LED32-A)") (class "Default")
      (node (ref "LED32") (pin "1") (pinfunction "A_1") (pintype "unspecified"))
      (node (ref "R18") (pin "1") (pinfunction "1_1") (pintype "input"))
    )
    (net (code "67") (name "Net-(LED33-C)") (class "Default")
      (node (ref "LED33") (pin "2") (pinfunction "C_2") (pintype "unspecified"))
      (node (ref "R2") (pin "1") (pinfunction "1_1") (pintype "input"))
    )
    (net (code "68") (name "Net-(LED34-A)") (class "Default")
      (node (ref "LED34") (pin "1") (pinfunction "A_1") (pintype "unspecified"))
      (node (ref "R2") (pin "2") (pinfunction "2_2") (pintype "input"))
    )
    (net (code "69") (name "Net-(LED34-C)") (class "Default")
      (node (ref "LED34") (pin "2") (pinfunction "C_2") (pintype "unspecified"))
      (node (ref "R15") (pin "1") (pinfunction "1_1") (pintype "input"))
    )
    (net (code "70") (name "Net-(LED35-A)") (class "Default")
      (node (ref "LED35") (pin "1") (pinfunction "A_1") (pintype "unspecified"))
      (node (ref "R16") (pin "1") (pinfunction "1_1") (pintype "input"))
    )
    (net (code "71") (name "Net-(LED35-C)") (class "Default")
      (node (ref "LED35") (pin "2") (pinfunction "C_2") (pintype "unspecified"))
      (node (ref "LED36") (pin "1") (pinfunction "A_1") (pintype "unspecified"))
    )
    (net (code "72") (name "Net-(LED36-C)") (class "Default")
      (node (ref "LED36") (pin "2") (pinfunction "C_2") (pintype "unspecified"))
      (node (ref "R3") (pin "1") (pinfunction "1_1") (pintype "input"))
    )
    (net (code "73") (name "Net-(LED37-A)") (class "Default")
      (node (ref "LED37") (pin "1") (pinfunction "A_1") (pintype "unspecified"))
      (node (ref "R3") (pin "2") (pinfunction "2_2") (pintype "input"))
    )
    (net (code "74") (name "Net-(LED37-C)") (class "Default")
      (node (ref "LED37") (pin "2") (pinfunction "C_2") (pintype "unspecified"))
      (node (ref "R23") (pin "1") (pinfunction "1_1") (pintype "input"))
    )
    (net (code "75") (name "Net-(LED38-A)") (class "Default")
      (node (ref "LED38") (pin "1") (pinfunction "A_1") (pintype "unspecified"))
      (node (ref "R24") (pin "1") (pinfunction "1_1") (pintype "input"))
    )
    (net (code "76") (name "Net-(LED38-C)") (class "Default")
      (node (ref "LED38") (pin "2") (pinfunction "C_2") (pintype "unspecified"))
      (node (ref "LED39") (pin "1") (pinfunction "A_1") (pintype "unspecified"))
    )
    (net (code "77") (name "Net-(LED39-C)") (class "Default")
      (node (ref "LED39") (pin "2") (pinfunction "C_2") (pintype "unspecified"))
      (node (ref "LED40") (pin "1") (pinfunction "A_1") (pintype "unspecified"))
    )
    (net (code "78") (name "Net-(LED40-C)") (class "Default")
      (node (ref "LED40") (pin "2") (pinfunction "C_2") (pintype "unspecified"))
      (node (ref "R31") (pin "1") (pinfunction "1_1") (pintype "input"))
    )
    (net (code "79") (name "Net-(LED41-A)") (class "Default")
      (node (ref "LED41") (pin "1") (pinfunction "A_1") (pintype "unspecified"))
      (node (ref "R36") (pin "1") (pinfunction "1_1") (pintype "input"))
    )
    (net (code "80") (name "Net-(LED41-C)") (class "Default")
      (node (ref "LED41") (pin "2") (pinfunction "C_2") (pintype "unspecified"))
      (node (ref "LED42") (pin "1") (pinfunction "A_1") (pintype "unspecified"))
    )
    (net (code "81") (name "Net-(LED42-C)") (class "Default")
      (node (ref "LED42") (pin "2") (pinfunction "C_2") (pintype "unspecified"))
      (node (ref "LED43") (pin "1") (pinfunction "A_1") (pintype "unspecified"))
    )
    (net (code "82") (name "Net-(LED43-C)") (class "Default")
      (node (ref "LED43") (pin "2") (pinfunction "C_2") (pintype "unspecified"))
      (node (ref "LED44") (pin "1") (pinfunction "A_1") (pintype "unspecified"))
    )
    (net (code "83") (name "Net-(LED44-C)") (class "Default")
      (node (ref "LED44") (pin "2") (pinfunction "C_2") (pintype "unspecified"))
      (node (ref "R12") (pin "1") (pinfunction "1_1") (pintype "input"))
    )
    (net (code "84") (name "Net-(LED45-A)") (class "Default")
      (node (ref "LED45") (pin "1") (pinfunction "A_1") (pintype "unspecified"))
      (node (ref "R12") (pin "2") (pinfunction "2_2") (pintype "input"))
    )
    (net (code "85") (name "Net-(LED45-C)") (class "Default")
      (node (ref "LED45") (pin "2") (pinfunction "C_2") (pintype "unspecified"))
      (node (ref "R25") (pin "1") (pinfunction "1_1") (pintype "input"))
    )
    (net (code "86") (name "Net-(LED46-A)") (class "Default")
      (node (ref "LED46") (pin "1") (pinfunction "A_1") (pintype "unspecified"))
      (node (ref "R26") (pin "1") (pinfunction "1_1") (pintype "input"))
    )
    (net (code "87") (name "Net-(LED46-C)") (class "Default")
      (node (ref "LED46") (pin "2") (pinfunction "C_2") (pintype "unspecified"))
      (node (ref "R4") (pin "1") (pinfunction "1_1") (pintype "input"))
    )
    (net (code "88") (name "Net-(LED47-A)") (class "Default")
      (node (ref "LED47") (pin "1") (pinfunction "A_1") (pintype "unspecified"))
      (node (ref "R4") (pin "2") (pinfunction "2_2") (pintype "input"))
    )
    (net (code "89") (name "Net-(LED47-C)") (class "Default")
      (node (ref "LED47") (pin "2") (pinfunction "C_2") (pintype "unspecified"))
      (node (ref "LED48") (pin "1") (pinfunction "A_1") (pintype "unspecified"))
    )
    (net (code "90") (name "Net-(LED48-C)") (class "Default")
      (node (ref "LED48") (pin "2") (pinfunction "C_2") (pintype "unspecified"))
      (node (ref "R35") (pin "1") (pinfunction "1_1") (pintype "input"))
    )
    (net (code "91") (name "Net-(LED49-A)") (class "Default")
      (node (ref "LED49") (pin "1") (pinfunction "A_1") (pintype "unspecified"))
      (node (ref "R38") (pin "1") (pinfunction "1_1") (pintype "input"))
    )
    (net (code "92") (name "Net-(LED49-C)") (class "Default")
      (node (ref "LED49") (pin "2") (pinfunction "C_2") (pintype "unspecified"))
      (node (ref "LED50") (pin "1") (pinfunction "A_1") (pintype "unspecified"))
    )
    (net (code "93") (name "Net-(LED50-C)") (class "Default")
      (node (ref "LED50") (pin "2") (pinfunction "C_2") (pintype "unspecified"))
      (node (ref "LED51") (pin "1") (pinfunction "A_1") (pintype "unspecified"))
    )
    (net (code "94") (name "Net-(LED51-C)") (class "Default")
      (node (ref "LED51") (pin "2") (pinfunction "C_2") (pintype "unspecified"))
      (node (ref "LED52") (pin "1") (pinfunction "A_1") (pintype "unspecified"))
    )
    (net (code "95") (name "Net-(LED52-C)") (class "Default")
      (node (ref "LED52") (pin "2") (pinfunction "C_2") (pintype "unspecified"))
      (node (ref "R6") (pin "1") (pinfunction "1_1") (pintype "input"))
    )
    (net (code "96") (name "Net-(LED53-A)") (class "Default")
      (node (ref "LED53") (pin "1") (pinfunction "A_1") (pintype "unspecified"))
      (node (ref "R6") (pin "2") (pinfunction "2_2") (pintype "input"))
    )
    (net (code "97") (name "Net-(LED53-C)") (class "Default")
      (node (ref "LED53") (pin "2") (pinfunction "C_2") (pintype "unspecified"))
      (node (ref "LED54") (pin "1") (pinfunction "A_1") (pintype "unspecified"))
    )
    (net (code "98") (name "Net-(LED54-C)") (class "Default")
      (node (ref "LED54") (pin "2") (pinfunction "C_2") (pintype "unspecified"))
      (node (ref "LED55") (pin "1") (pinfunction "A_1") (pintype "unspecified"))
    )
    (net (code "99") (name "Net-(LED55-C)") (class "Default")
      (node (ref "LED55") (pin "2") (pinfunction "C_2") (pintype "unspecified"))
      (node (ref "LED56") (pin "1") (pinfunction "A_1") (pintype "unspecified"))
    )
    (net (code "100") (name "Net-(LED57-A)") (class "Default")
      (node (ref "LED57") (pin "1") (pinfunction "A_1") (pintype "unspecified"))
      (node (ref "R30") (pin "1") (pinfunction "1_1") (pintype "input"))
    )
    (net (code "101") (name "Net-(LED57-C)") (class "Default")
      (node (ref "LED57") (pin "2") (pinfunction "C_2") (pintype "unspecified"))
      (node (ref "LED58") (pin "1") (pinfunction "A_1") (pintype "unspecified"))
    )
    (net (code "102") (name "Net-(LED58-C)") (class "Default")
      (node (ref "LED58") (pin "2") (pinfunction "C_2") (pintype "unspecified"))
      (node (ref "LED59") (pin "1") (pinfunction "A_1") (pintype "unspecified"))
    )
    (net (code "103") (name "Net-(LED59-C)") (class "Default")
      (node (ref "LED59") (pin "2") (pinfunction "C_2") (pintype "unspecified"))
      (node (ref "LED60") (pin "1") (pinfunction "A_1") (pintype "unspecified"))
    )
    (net (code "104") (name "Net-(LED60-C)") (class "Default")
      (node (ref "LED60") (pin "2") (pinfunction "C_2") (pintype "unspecified"))
      (node (ref "R10") (pin "1") (pinfunction "1_1") (pintype "input"))
    )
    (net (code "105") (name "Net-(LED61-A)") (class "Default")
      (node (ref "LED61") (pin "1") (pinfunction "A_1") (pintype "unspecified"))
      (node (ref "R10") (pin "2") (pinfunction "2_2") (pintype "input"))
    )
    (net (code "106") (name "Net-(LED61-C)") (class "Default")
      (node (ref "LED61") (pin "2") (pinfunction "C_2") (pintype "unspecified"))
      (node (ref "LED62") (pin "1") (pinfunction "A_1") (pintype "unspecified"))
    )
    (net (code "107") (name "Net-(LED62-C)") (class "Default")
      (node (ref "LED62") (pin "2") (pinfunction "C_2") (pintype "unspecified"))
      (node (ref "LED63") (pin "1") (pinfunction "A_1") (pintype "unspecified"))
    )
    (net (code "108") (name "Net-(LED63-C)") (class "Default")
      (node (ref "LED63") (pin "2") (pinfunction "C_2") (pintype "unspecified"))
      (node (ref "LED64") (pin "1") (pinfunction "A_1") (pintype "unspecified"))
    )
    (net (code "109") (name "Net-(R7-Pad2)") (class "Default")
      (node (ref "R7") (pin "2") (pinfunction "2_2") (pintype "input"))
      (node (ref "R8") (pin "2") (pinfunction "2_2") (pintype "input"))
    )
    (net (code "110") (name "Net-(R13-Pad2)") (class "Default")
      (node (ref "R13") (pin "2") (pinfunction "2_2") (pintype "input"))
      (node (ref "R14") (pin "2") (pinfunction "2_2") (pintype "input"))
    )
    (net (code "111") (name "Net-(R15-Pad2)") (class "Default")
      (node (ref "R15") (pin "2") (pinfunction "2_2") (pintype "input"))
      (node (ref "R16") (pin "2") (pinfunction "2_2") (pintype "input"))
    )
    (net (code "112") (name "Net-(R17-Pad2)") (class "Default")
      (node (ref "R17") (pin "2") (pinfunction "2_2") (pintype "input"))
      (node (ref "R18") (pin "2") (pinfunction "2_2") (pintype "input"))
    )
    (net (code "113") (name "Net-(R21-Pad2)") (class "Default")
      (node (ref "R21") (pin "2") (pinfunction "2_2") (pintype "input"))
      (node (ref "R22") (pin "2") (pinfunction "2_2") (pintype "input"))
    )
    (net (code "114") (name "Net-(R23-Pad2)") (class "Default")
      (node (ref "R23") (pin "2") (pinfunction "2_2") (pintype "input"))
      (node (ref "R24") (pin "2") (pinfunction "2_2") (pintype "input"))
    )
    (net (code "115") (name "Net-(R25-Pad2)") (class "Default")
      (node (ref "R25") (pin "2") (pinfunction "2_2") (pintype "input"))
      (node (ref "R26") (pin "2") (pinfunction "2_2") (pintype "input"))
    )
    (net (code "116") (name "Net-(R28-Pad2)") (class "Default")
      (node (ref "R28") (pin "2") (pinfunction "2_2") (pintype "input"))
      (node (ref "R29") (pin "2") (pinfunction "2_2") (pintype "input"))
    )
    (net (code "117") (name "Net-(R38-Pad2)") (class "Default")
      (node (ref "R38") (pin "2") (pinfunction "2_2") (pintype "input"))
      (node (ref "R39") (pin "2") (pinfunction "2_2") (pintype "input"))
    )
    (net (code "118") (name "unconnected-(R1-Pad2)") (class "Default")
      (node (ref "R1") (pin "2") (pinfunction "2_2") (pintype "unspecified"))
    )
  )
)
